# Servo_update.net
KiCad netlist of a schematic drawn in EAGLE
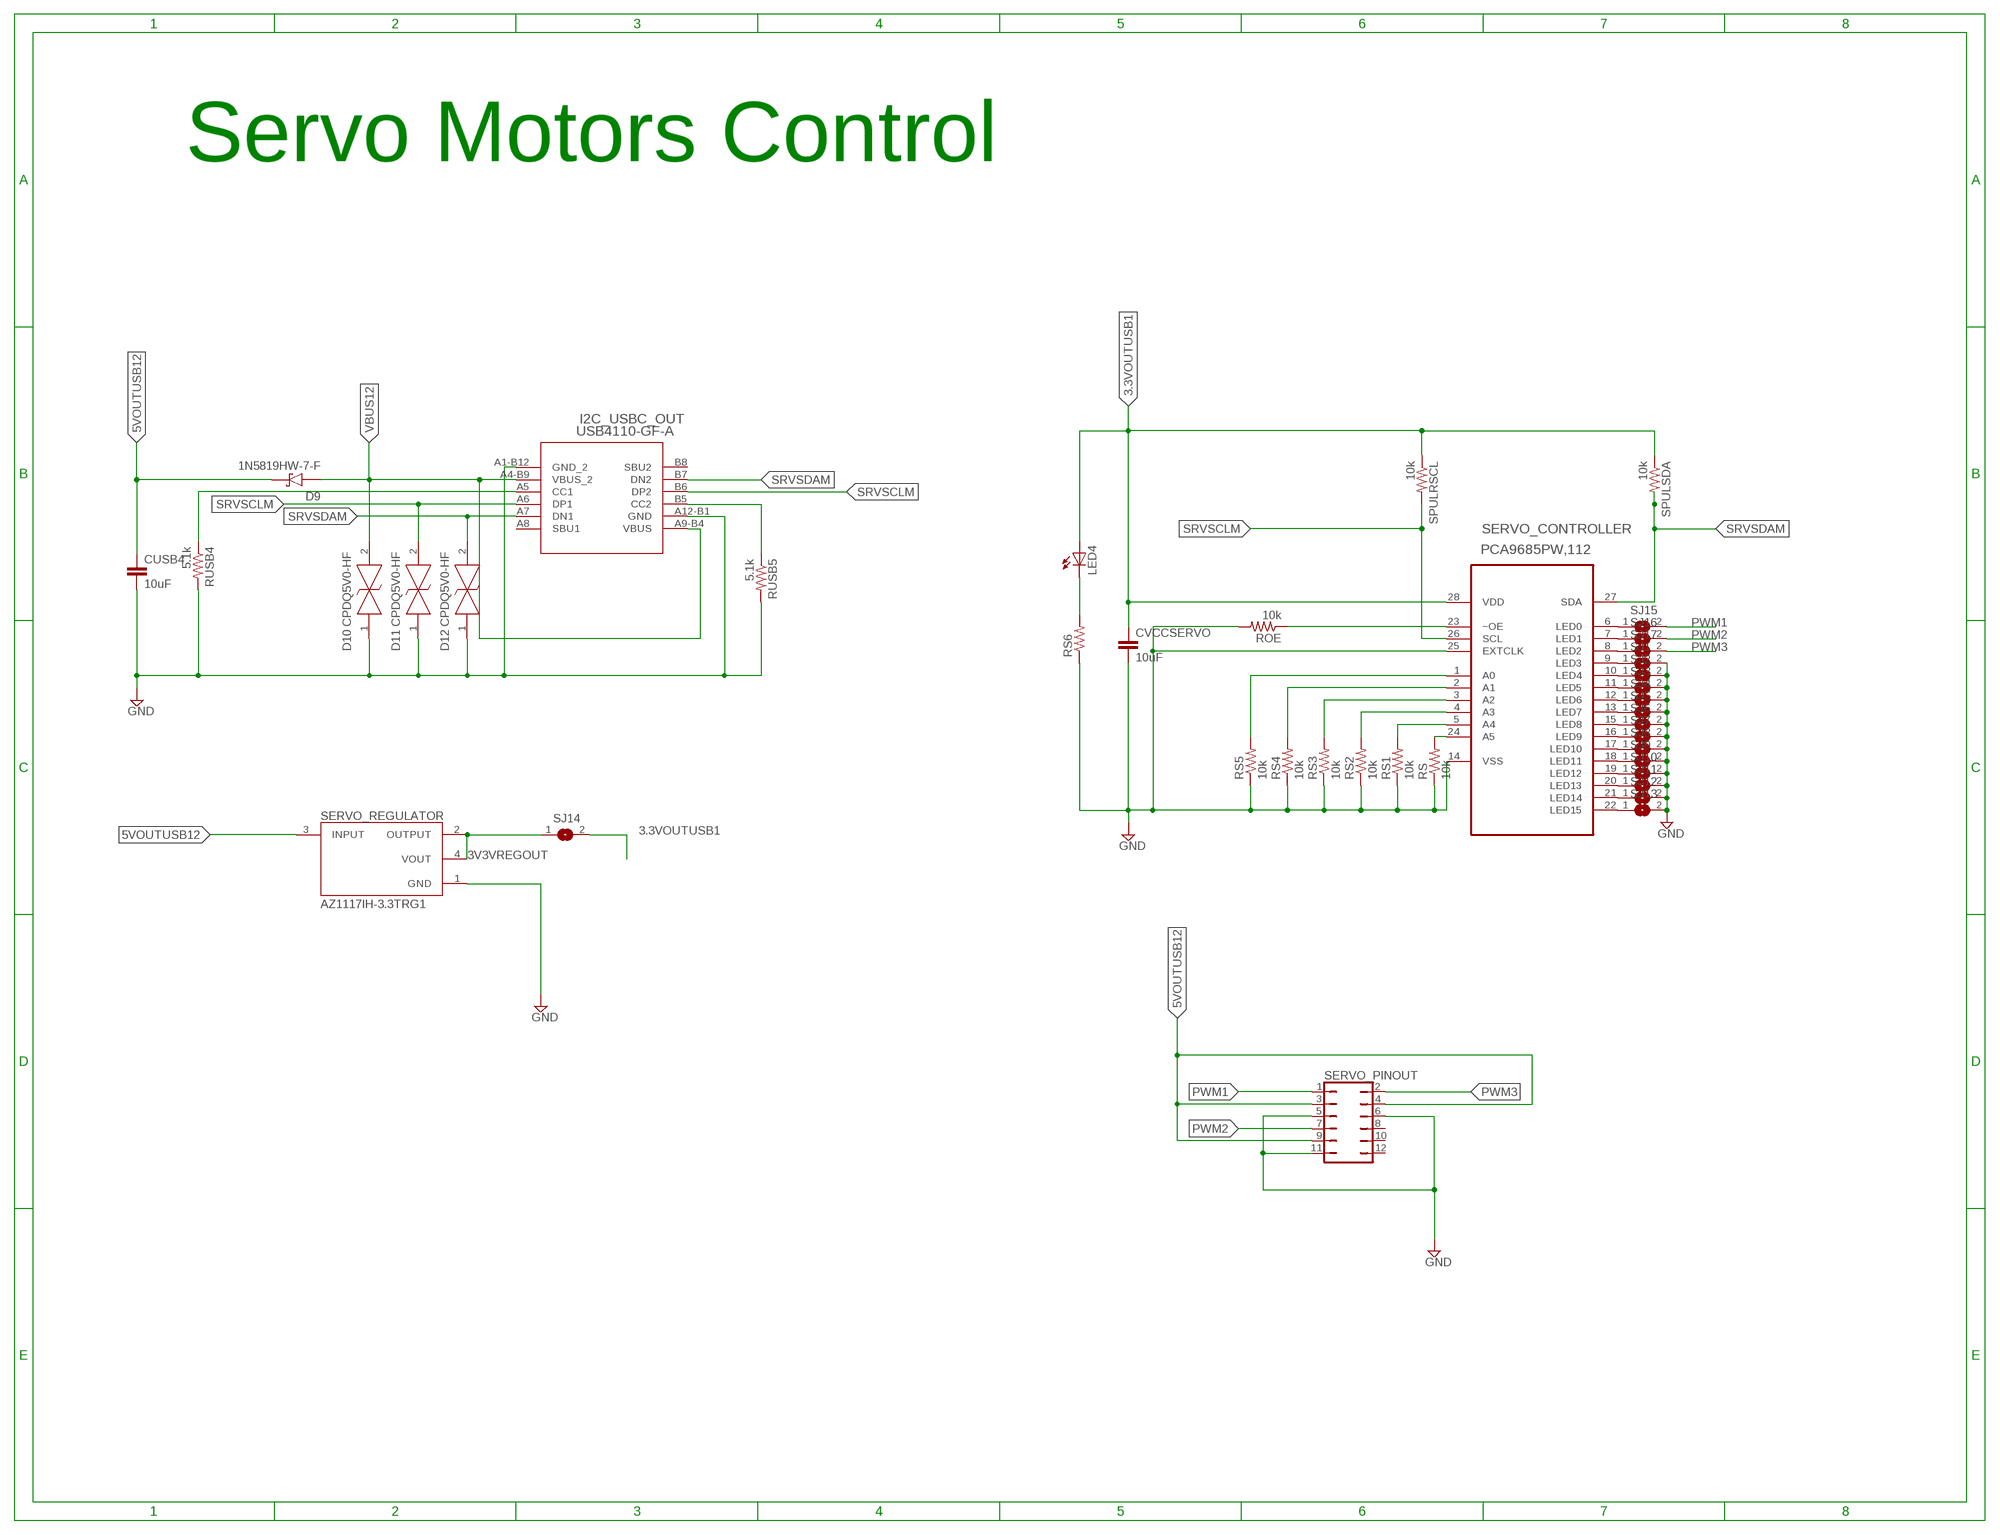
[diagram p0: schematic, sheet 1]

(export (version "E")
  (design (tool "Eeschema 10.0.6"))
  (components
    (comp (ref "CUSB4")
      (value "10uF")
      (footprint "eagle-import:C0805")
      (libsource (lib "eagle-import") (part "C-EUC0805"))
    )
    (comp (ref "CVCCSERVO")
      (value "10uF")
      (footprint "eagle-import:C0805")
      (libsource (lib "eagle-import") (part "C-EUC0805"))
    )
    (comp (ref "D9")
      (value "1N5819HW-7-F")
      (footprint "eagle-import:SOD3715X145N")
      (fields (field (name "MF") "Diodes Inc."))
      (libsource (lib "eagle-import") (part "1N5819HW-7-F"))
    )
    (comp (ref "D10")
      (value "CPDQ5V0-HF")
      (footprint "eagle-import:MBTB-D-SOD-923F-IMP-0402")
      (fields (field (name "MF") "Comchip Technology"))
      (libsource (lib "eagle-import") (part "CPDQ5V0-HF"))
    )
    (comp (ref "D11")
      (value "CPDQ5V0-HF")
      (footprint "eagle-import:MBTB-D-SOD-923F-IMP-0402")
      (fields (field (name "MF") "Comchip Technology"))
      (libsource (lib "eagle-import") (part "CPDQ5V0-HF"))
    )
    (comp (ref "D12")
      (value "CPDQ5V0-HF")
      (footprint "eagle-import:MBTB-D-SOD-923F-IMP-0402")
      (fields (field (name "MF") "Comchip Technology"))
      (libsource (lib "eagle-import") (part "CPDQ5V0-HF"))
    )
    (comp (ref "I2C_USBC_OUT")
      (value "USB4110-GF-A")
      (footprint "eagle-import:USB4110-GF-A_GCT")
      (fields (field (name "COPYRIGHT") "Copyright (C) 2023 Ultra Librarian. All rights reserved."))
      (libsource (lib "eagle-import") (part "USB4110-GF-A"))
    )
    (comp (ref "LED4")
      (value "LED")
      (footprint "eagle-import:SMARTLED-TTW")
      (libsource (lib "eagle-import") (part "LED"))
    )
    (comp (ref "ROE")
      (value "10k")
      (footprint "eagle-import:M0805")
      (libsource (lib "eagle-import") (part "R-US_M0805"))
    )
    (comp (ref "RS")
      (value "10k")
      (footprint "eagle-import:R0805")
      (libsource (lib "eagle-import") (part "R-US_R0805"))
    )
    (comp (ref "RS1")
      (value "10k")
      (footprint "eagle-import:R0805")
      (libsource (lib "eagle-import") (part "R-US_R0805"))
    )
    (comp (ref "RS2")
      (value "10k")
      (footprint "eagle-import:R0805")
      (libsource (lib "eagle-import") (part "R-US_R0805"))
    )
    (comp (ref "RS3")
      (value "10k")
      (footprint "eagle-import:R0805")
      (libsource (lib "eagle-import") (part "R-US_R0805"))
    )
    (comp (ref "RS4")
      (value "10k")
      (footprint "eagle-import:R0805")
      (libsource (lib "eagle-import") (part "R-US_R0805"))
    )
    (comp (ref "RS5")
      (value "10k")
      (footprint "eagle-import:R0805")
      (libsource (lib "eagle-import") (part "R-US_R0805"))
    )
    (comp (ref "RS6")
      (value "2.2k")
      (footprint "eagle-import:R0805")
      (libsource (lib "eagle-import") (part "R-US_R0805"))
    )
    (comp (ref "RUSB4")
      (value "5.1k")
      (footprint "eagle-import:M0805")
      (libsource (lib "eagle-import") (part "R-US_M0805"))
    )
    (comp (ref "RUSB5")
      (value "5.1k")
      (footprint "eagle-import:M0805")
      (libsource (lib "eagle-import") (part "R-US_M0805"))
    )
    (comp (ref "SERVO_CONTROLLER")
      (value "PCA9685PW,112")
      (footprint "eagle-import:SOP65P640X110-28N")
      (fields (field (name "MF") "NXP USA"))
      (libsource (lib "eagle-import") (part "PCA9685PW,112"))
    )
    (comp (ref "SERVO_PINOUT")
      (value "JP6Q")
      (footprint "eagle-import:JP6Q")
      (libsource (lib "eagle-import") (part "JP6Q"))
    )
    (comp (ref "SERVO_REGULATOR")
      (value "AZ1117IH-3.3TRG1")
      (footprint "eagle-import:SOT230P700X185-4N")
      (fields (field (name "MF") "Diodes Inc."))
      (libsource (lib "eagle-import") (part "AZ1117IH-3.3TRG1"))
    )
    (comp (ref "SJ1") (value "SJ") (footprint "eagle-import:SJ") (libsource (lib "eagle-import") (part "SJ")))
    (comp (ref "SJ2") (value "SJ") (footprint "eagle-import:SJ") (libsource (lib "eagle-import") (part "SJ")))
    (comp (ref "SJ3") (value "SJ") (footprint "eagle-import:SJ") (libsource (lib "eagle-import") (part "SJ")))
    (comp (ref "SJ4") (value "SJ") (footprint "eagle-import:SJ") (libsource (lib "eagle-import") (part "SJ")))
    (comp (ref "SJ5") (value "SJ") (footprint "eagle-import:SJ") (libsource (lib "eagle-import") (part "SJ")))
    (comp (ref "SJ6") (value "SJ") (footprint "eagle-import:SJ") (libsource (lib "eagle-import") (part "SJ")))
    (comp (ref "SJ7") (value "SJ") (footprint "eagle-import:SJ") (libsource (lib "eagle-import") (part "SJ")))
    (comp (ref "SJ8") (value "SJ") (footprint "eagle-import:SJ") (libsource (lib "eagle-import") (part "SJ")))
    (comp (ref "SJ9") (value "SJ") (footprint "eagle-import:SJ") (libsource (lib "eagle-import") (part "SJ")))
    (comp (ref "SJ10")
      (value "SJ")
      (footprint "eagle-import:SJ")
      (libsource (lib "eagle-import") (part "SJ"))
    )
    (comp (ref "SJ11")
      (value "SJ")
      (footprint "eagle-import:SJ")
      (libsource (lib "eagle-import") (part "SJ"))
    )
    (comp (ref "SJ12")
      (value "SJ")
      (footprint "eagle-import:SJ")
      (libsource (lib "eagle-import") (part "SJ"))
    )
    (comp (ref "SJ13")
      (value "SJ")
      (footprint "eagle-import:SJ")
      (libsource (lib "eagle-import") (part "SJ"))
    )
    (comp (ref "SJ14")
      (value "SJ")
      (footprint "eagle-import:SJ")
      (libsource (lib "eagle-import") (part "SJ"))
    )
    (comp (ref "SJ15")
      (value "SJ")
      (footprint "eagle-import:SJ")
      (libsource (lib "eagle-import") (part "SJ"))
    )
    (comp (ref "SJ16")
      (value "SJ")
      (footprint "eagle-import:SJ")
      (libsource (lib "eagle-import") (part "SJ"))
    )
    (comp (ref "SJ17")
      (value "SJ")
      (footprint "eagle-import:SJ")
      (libsource (lib "eagle-import") (part "SJ"))
    )
    (comp (ref "SPULRSCL")
      (value "10k")
      (footprint "eagle-import:M0805")
      (libsource (lib "eagle-import") (part "R-US_M0805"))
    )
    (comp (ref "SPULSDA")
      (value "10k")
      (footprint "eagle-import:M0805")
      (libsource (lib "eagle-import") (part "R-US_M0805"))
    )
  )
  (nets
    (net (code "1") (name "/3V3VREGOUT") (class "Default")
      (node (ref "SERVO_REGULATOR") (pin "2") (pinfunction "OUTPUT_2") (pintype "output"))
      (node (ref "SERVO_REGULATOR") (pin "4") (pinfunction "VOUT_4") (pintype "output"))
      (node (ref "SJ14") (pin "1") (pinfunction "1_1") (pintype "passive"))
    )
    (net (code "2") (name "3.3VOUTUSB1") (class "Default")
      (node (ref "CVCCSERVO") (pin "1") (pinfunction "1_1") (pintype "passive"))
      (node (ref "LED4") (pin "A@1") (pinfunction "A_A@1") (pintype "passive"))
      (node (ref "SERVO_CONTROLLER") (pin "28") (pinfunction "VDD_28") (pintype "power_in"))
      (node (ref "SJ14") (pin "2") (pinfunction "2_2") (pintype "passive"))
      (node (ref "SPULRSCL") (pin "1") (pinfunction "1_1") (pintype "passive"))
      (node (ref "SPULSDA") (pin "1") (pinfunction "1_1") (pintype "passive"))
    )
    (net (code "3") (name "5VOUTUSB12") (class "Default")
      (node (ref "CUSB4") (pin "1") (pinfunction "1_1") (pintype "passive"))
      (node (ref "D9") (pin "C") (pinfunction "K_C") (pintype "passive"))
      (node (ref "SERVO_PINOUT") (pin "3") (pinfunction "3_3") (pintype "passive"))
      (node (ref "SERVO_PINOUT") (pin "4") (pinfunction "4_4") (pintype "passive"))
      (node (ref "SERVO_PINOUT") (pin "9") (pinfunction "9_9") (pintype "passive"))
      (node (ref "SERVO_REGULATOR") (pin "3") (pinfunction "INPUT_3") (pintype "input"))
    )
    (net (code "4") (name "GND") (class "Default")
      (node (ref "CUSB4") (pin "2") (pinfunction "2_2") (pintype "passive"))
      (node (ref "CVCCSERVO") (pin "2") (pinfunction "2_2") (pintype "passive"))
      (node (ref "D10") (pin "1") (pinfunction "K_1") (pintype "bidirectional"))
      (node (ref "D11") (pin "1") (pinfunction "K_1") (pintype "bidirectional"))
      (node (ref "D12") (pin "1") (pinfunction "K_1") (pintype "bidirectional"))
      (node (ref "I2C_USBC_OUT") (pin "A1-B12") (pinfunction "GND_2_A1-B12") (pintype "passive"))
      (node (ref "I2C_USBC_OUT") (pin "A12-B1") (pinfunction "GND_A12-B1") (pintype "passive"))
      (node (ref "ROE") (pin "2") (pinfunction "2_2") (pintype "passive"))
      (node (ref "RS") (pin "1") (pinfunction "1_1") (pintype "passive"))
      (node (ref "RS1") (pin "1") (pinfunction "1_1") (pintype "passive"))
      (node (ref "RS2") (pin "1") (pinfunction "1_1") (pintype "passive"))
      (node (ref "RS3") (pin "1") (pinfunction "1_1") (pintype "passive"))
      (node (ref "RS4") (pin "1") (pinfunction "1_1") (pintype "passive"))
      (node (ref "RS5") (pin "1") (pinfunction "1_1") (pintype "passive"))
      (node (ref "RS6") (pin "1") (pinfunction "1_1") (pintype "passive"))
      (node (ref "RUSB4") (pin "2") (pinfunction "2_2") (pintype "passive"))
      (node (ref "RUSB5") (pin "2") (pinfunction "2_2") (pintype "passive"))
      (node (ref "SERVO_CONTROLLER") (pin "14") (pinfunction "VSS_14") (pintype "passive"))
      (node (ref "SERVO_CONTROLLER") (pin "25") (pinfunction "EXTCLK_25") (pintype "input"))
      (node (ref "SERVO_PINOUT") (pin "11") (pinfunction "11_11") (pintype "passive"))
      (node (ref "SERVO_PINOUT") (pin "5") (pinfunction "5_5") (pintype "passive"))
      (node (ref "SERVO_PINOUT") (pin "6") (pinfunction "6_6") (pintype "passive"))
      (node (ref "SERVO_REGULATOR") (pin "1") (pinfunction "GND_1") (pintype "power_in"))
      (node (ref "SJ1") (pin "2") (pinfunction "2_2") (pintype "passive"))
      (node (ref "SJ10") (pin "2") (pinfunction "2_2") (pintype "passive"))
      (node (ref "SJ11") (pin "2") (pinfunction "2_2") (pintype "passive"))
      (node (ref "SJ12") (pin "2") (pinfunction "2_2") (pintype "passive"))
      (node (ref "SJ13") (pin "2") (pinfunction "2_2") (pintype "passive"))
      (node (ref "SJ2") (pin "2") (pinfunction "2_2") (pintype "passive"))
      (node (ref "SJ3") (pin "2") (pinfunction "2_2") (pintype "passive"))
      (node (ref "SJ4") (pin "2") (pinfunction "2_2") (pintype "passive"))
      (node (ref "SJ5") (pin "2") (pinfunction "2_2") (pintype "passive"))
      (node (ref "SJ6") (pin "2") (pinfunction "2_2") (pintype "passive"))
      (node (ref "SJ7") (pin "2") (pinfunction "2_2") (pintype "passive"))
      (node (ref "SJ8") (pin "2") (pinfunction "2_2") (pintype "passive"))
      (node (ref "SJ9") (pin "2") (pinfunction "2_2") (pintype "passive"))
    )
    (net (code "5") (name "Net-(I2C_USBC_OUT-CC1)") (class "Default")
      (node (ref "I2C_USBC_OUT") (pin "A5") (pinfunction "CC1_A5") (pintype "bidirectional"))
      (node (ref "RUSB4") (pin "1") (pinfunction "1_1") (pintype "passive"))
    )
    (net (code "6") (name "Net-(I2C_USBC_OUT-CC2)") (class "Default")
      (node (ref "I2C_USBC_OUT") (pin "B5") (pinfunction "CC2_B5") (pintype "bidirectional"))
      (node (ref "RUSB5") (pin "1") (pinfunction "1_1") (pintype "passive"))
    )
    (net (code "7") (name "Net-(LED4-C)") (class "Default")
      (node (ref "LED4") (pin "C@1") (pinfunction "C_C@1") (pintype "passive"))
      (node (ref "RS6") (pin "2") (pinfunction "2_2") (pintype "passive"))
    )
    (net (code "8") (name "Net-(SERVO_CONTROLLER-A0)") (class "Default")
      (node (ref "RS5") (pin "2") (pinfunction "2_2") (pintype "passive"))
      (node (ref "SERVO_CONTROLLER") (pin "1") (pinfunction "A0_1") (pintype "input"))
    )
    (net (code "9") (name "Net-(SERVO_CONTROLLER-A1)") (class "Default")
      (node (ref "RS4") (pin "2") (pinfunction "2_2") (pintype "passive"))
      (node (ref "SERVO_CONTROLLER") (pin "2") (pinfunction "A1_2") (pintype "input"))
    )
    (net (code "10") (name "Net-(SERVO_CONTROLLER-A2)") (class "Default")
      (node (ref "RS3") (pin "2") (pinfunction "2_2") (pintype "passive"))
      (node (ref "SERVO_CONTROLLER") (pin "3") (pinfunction "A2_3") (pintype "input"))
    )
    (net (code "11") (name "Net-(SERVO_CONTROLLER-A3)") (class "Default")
      (node (ref "RS2") (pin "2") (pinfunction "2_2") (pintype "passive"))
      (node (ref "SERVO_CONTROLLER") (pin "4") (pinfunction "A3_4") (pintype "input"))
    )
    (net (code "12") (name "Net-(SERVO_CONTROLLER-A4)") (class "Default")
      (node (ref "RS1") (pin "2") (pinfunction "2_2") (pintype "passive"))
      (node (ref "SERVO_CONTROLLER") (pin "5") (pinfunction "A4_5") (pintype "input"))
    )
    (net (code "13") (name "Net-(SERVO_CONTROLLER-A5)") (class "Default")
      (node (ref "RS") (pin "2") (pinfunction "2_2") (pintype "passive"))
      (node (ref "SERVO_CONTROLLER") (pin "24") (pinfunction "A5_24") (pintype "input"))
    )
    (net (code "14") (name "Net-(SERVO_CONTROLLER-LED0)") (class "Default")
      (node (ref "SERVO_CONTROLLER") (pin "6") (pinfunction "LED0_6") (pintype "output"))
      (node (ref "SJ15") (pin "1") (pinfunction "1_1") (pintype "passive"))
    )
    (net (code "15") (name "Net-(SERVO_CONTROLLER-LED1)") (class "Default")
      (node (ref "SERVO_CONTROLLER") (pin "7") (pinfunction "LED1_7") (pintype "output"))
      (node (ref "SJ16") (pin "1") (pinfunction "1_1") (pintype "passive"))
    )
    (net (code "16") (name "Net-(SERVO_CONTROLLER-LED2)") (class "Default")
      (node (ref "SERVO_CONTROLLER") (pin "8") (pinfunction "LED2_8") (pintype "output"))
      (node (ref "SJ17") (pin "1") (pinfunction "1_1") (pintype "passive"))
    )
    (net (code "17") (name "Net-(SERVO_CONTROLLER-LED3)") (class "Default")
      (node (ref "SERVO_CONTROLLER") (pin "9") (pinfunction "LED3_9") (pintype "output"))
      (node (ref "SJ1") (pin "1") (pinfunction "1_1") (pintype "passive"))
    )
    (net (code "18") (name "Net-(SERVO_CONTROLLER-LED4)") (class "Default")
      (node (ref "SERVO_CONTROLLER") (pin "10") (pinfunction "LED4_10") (pintype "output"))
      (node (ref "SJ2") (pin "1") (pinfunction "1_1") (pintype "passive"))
    )
    (net (code "19") (name "Net-(SERVO_CONTROLLER-LED5)") (class "Default")
      (node (ref "SERVO_CONTROLLER") (pin "11") (pinfunction "LED5_11") (pintype "output"))
      (node (ref "SJ3") (pin "1") (pinfunction "1_1") (pintype "passive"))
    )
    (net (code "20") (name "Net-(SERVO_CONTROLLER-LED6)") (class "Default")
      (node (ref "SERVO_CONTROLLER") (pin "12") (pinfunction "LED6_12") (pintype "output"))
      (node (ref "SJ4") (pin "1") (pinfunction "1_1") (pintype "passive"))
    )
    (net (code "21") (name "Net-(SERVO_CONTROLLER-LED7)") (class "Default")
      (node (ref "SERVO_CONTROLLER") (pin "13") (pinfunction "LED7_13") (pintype "output"))
      (node (ref "SJ5") (pin "1") (pinfunction "1_1") (pintype "passive"))
    )
    (net (code "22") (name "Net-(SERVO_CONTROLLER-LED8)") (class "Default")
      (node (ref "SERVO_CONTROLLER") (pin "15") (pinfunction "LED8_15") (pintype "output"))
      (node (ref "SJ6") (pin "1") (pinfunction "1_1") (pintype "passive"))
    )
    (net (code "23") (name "Net-(SERVO_CONTROLLER-LED9)") (class "Default")
      (node (ref "SERVO_CONTROLLER") (pin "16") (pinfunction "LED9_16") (pintype "output"))
      (node (ref "SJ7") (pin "1") (pinfunction "1_1") (pintype "passive"))
    )
    (net (code "24") (name "Net-(SERVO_CONTROLLER-LED10)") (class "Default")
      (node (ref "SERVO_CONTROLLER") (pin "17") (pinfunction "LED10_17") (pintype "output"))
      (node (ref "SJ8") (pin "1") (pinfunction "1_1") (pintype "passive"))
    )
    (net (code "25") (name "Net-(SERVO_CONTROLLER-LED11)") (class "Default")
      (node (ref "SERVO_CONTROLLER") (pin "18") (pinfunction "LED11_18") (pintype "output"))
      (node (ref "SJ9") (pin "1") (pinfunction "1_1") (pintype "passive"))
    )
    (net (code "26") (name "Net-(SERVO_CONTROLLER-LED12)") (class "Default")
      (node (ref "SERVO_CONTROLLER") (pin "19") (pinfunction "LED12_19") (pintype "output"))
      (node (ref "SJ10") (pin "1") (pinfunction "1_1") (pintype "passive"))
    )
    (net (code "27") (name "Net-(SERVO_CONTROLLER-LED13)") (class "Default")
      (node (ref "SERVO_CONTROLLER") (pin "20") (pinfunction "LED13_20") (pintype "output"))
      (node (ref "SJ11") (pin "1") (pinfunction "1_1") (pintype "passive"))
    )
    (net (code "28") (name "Net-(SERVO_CONTROLLER-LED14)") (class "Default")
      (node (ref "SERVO_CONTROLLER") (pin "21") (pinfunction "LED14_21") (pintype "output"))
      (node (ref "SJ12") (pin "1") (pinfunction "1_1") (pintype "passive"))
    )
    (net (code "29") (name "Net-(SERVO_CONTROLLER-LED15)") (class "Default")
      (node (ref "SERVO_CONTROLLER") (pin "22") (pinfunction "LED15_22") (pintype "output"))
      (node (ref "SJ13") (pin "1") (pinfunction "1_1") (pintype "passive"))
    )
    (net (code "30") (name "Net-(SERVO_CONTROLLER-~{OE})") (class "Default")
      (node (ref "ROE") (pin "1") (pinfunction "1_1") (pintype "passive"))
      (node (ref "SERVO_CONTROLLER") (pin "23") (pinfunction "~{OE}_23") (pintype "input"))
    )
    (net (code "31") (name "PWM1") (class "Default")
      (node (ref "SERVO_PINOUT") (pin "1") (pinfunction "1_1") (pintype "passive"))
      (node (ref "SJ15") (pin "2") (pinfunction "2_2") (pintype "passive"))
    )
    (net (code "32") (name "PWM2") (class "Default")
      (node (ref "SERVO_PINOUT") (pin "7") (pinfunction "7_7") (pintype "passive"))
      (node (ref "SJ16") (pin "2") (pinfunction "2_2") (pintype "passive"))
    )
    (net (code "33") (name "PWM3") (class "Default")
      (node (ref "SERVO_PINOUT") (pin "2") (pinfunction "2_2") (pintype "passive"))
      (node (ref "SJ17") (pin "2") (pinfunction "2_2") (pintype "passive"))
    )
    (net (code "34") (name "SRVSCLM") (class "Default")
      (node (ref "D11") (pin "2") (pinfunction "A_2") (pintype "bidirectional"))
      (node (ref "I2C_USBC_OUT") (pin "A6") (pinfunction "DP1_A6") (pintype "bidirectional"))
      (node (ref "I2C_USBC_OUT") (pin "B6") (pinfunction "DP2_B6") (pintype "bidirectional"))
      (node (ref "SERVO_CONTROLLER") (pin "26") (pinfunction "SCL_26") (pintype "input"))
      (node (ref "SPULRSCL") (pin "2") (pinfunction "2_2") (pintype "passive"))
    )
    (net (code "35") (name "SRVSDAM") (class "Default")
      (node (ref "D12") (pin "2") (pinfunction "A_2") (pintype "bidirectional"))
      (node (ref "I2C_USBC_OUT") (pin "A7") (pinfunction "DN1_A7") (pintype "bidirectional"))
      (node (ref "I2C_USBC_OUT") (pin "B7") (pinfunction "DN2_B7") (pintype "bidirectional"))
      (node (ref "SERVO_CONTROLLER") (pin "27") (pinfunction "SDA_27") (pintype "bidirectional"))
      (node (ref "SPULSDA") (pin "2") (pinfunction "2_2") (pintype "passive"))
    )
    (net (code "36") (name "VBUS12") (class "Default")
      (node (ref "D10") (pin "2") (pinfunction "A_2") (pintype "bidirectional"))
      (node (ref "D9") (pin "A") (pinfunction "A_A") (pintype "passive"))
      (node (ref "I2C_USBC_OUT") (pin "A4-B9") (pinfunction "VBUS_2_A4-B9") (pintype "power_in"))
      (node (ref "I2C_USBC_OUT") (pin "A9-B4") (pinfunction "VBUS_A9-B4") (pintype "power_in"))
    )
    (net (code "37") (name "unconnected-(I2C_USBC_OUT-SBU1-PadA8)") (class "Default")
      (node (ref "I2C_USBC_OUT") (pin "A8") (pinfunction "SBU1_A8") (pintype "bidirectional"))
    )
    (net (code "38") (name "unconnected-(I2C_USBC_OUT-SBU2-PadB8)") (class "Default")
      (node (ref "I2C_USBC_OUT") (pin "B8") (pinfunction "SBU2_B8") (pintype "bidirectional"))
    )
    (net (code "39") (name "unconnected-(SERVO_PINOUT-Pad8)") (class "Default")
      (node (ref "SERVO_PINOUT") (pin "8") (pinfunction "8_8") (pintype "passive"))
    )
    (net (code "40") (name "unconnected-(SERVO_PINOUT-Pad10)") (class "Default")
      (node (ref "SERVO_PINOUT") (pin "10") (pinfunction "10_10") (pintype "passive"))
    )
    (net (code "41") (name "unconnected-(SERVO_PINOUT-Pad12)") (class "Default")
      (node (ref "SERVO_PINOUT") (pin "12") (pinfunction "12_12") (pintype "passive"))
    )
  )
)
